# 2025-03-23.net
KiCad netlist of a schematic drawn in EasyEDA
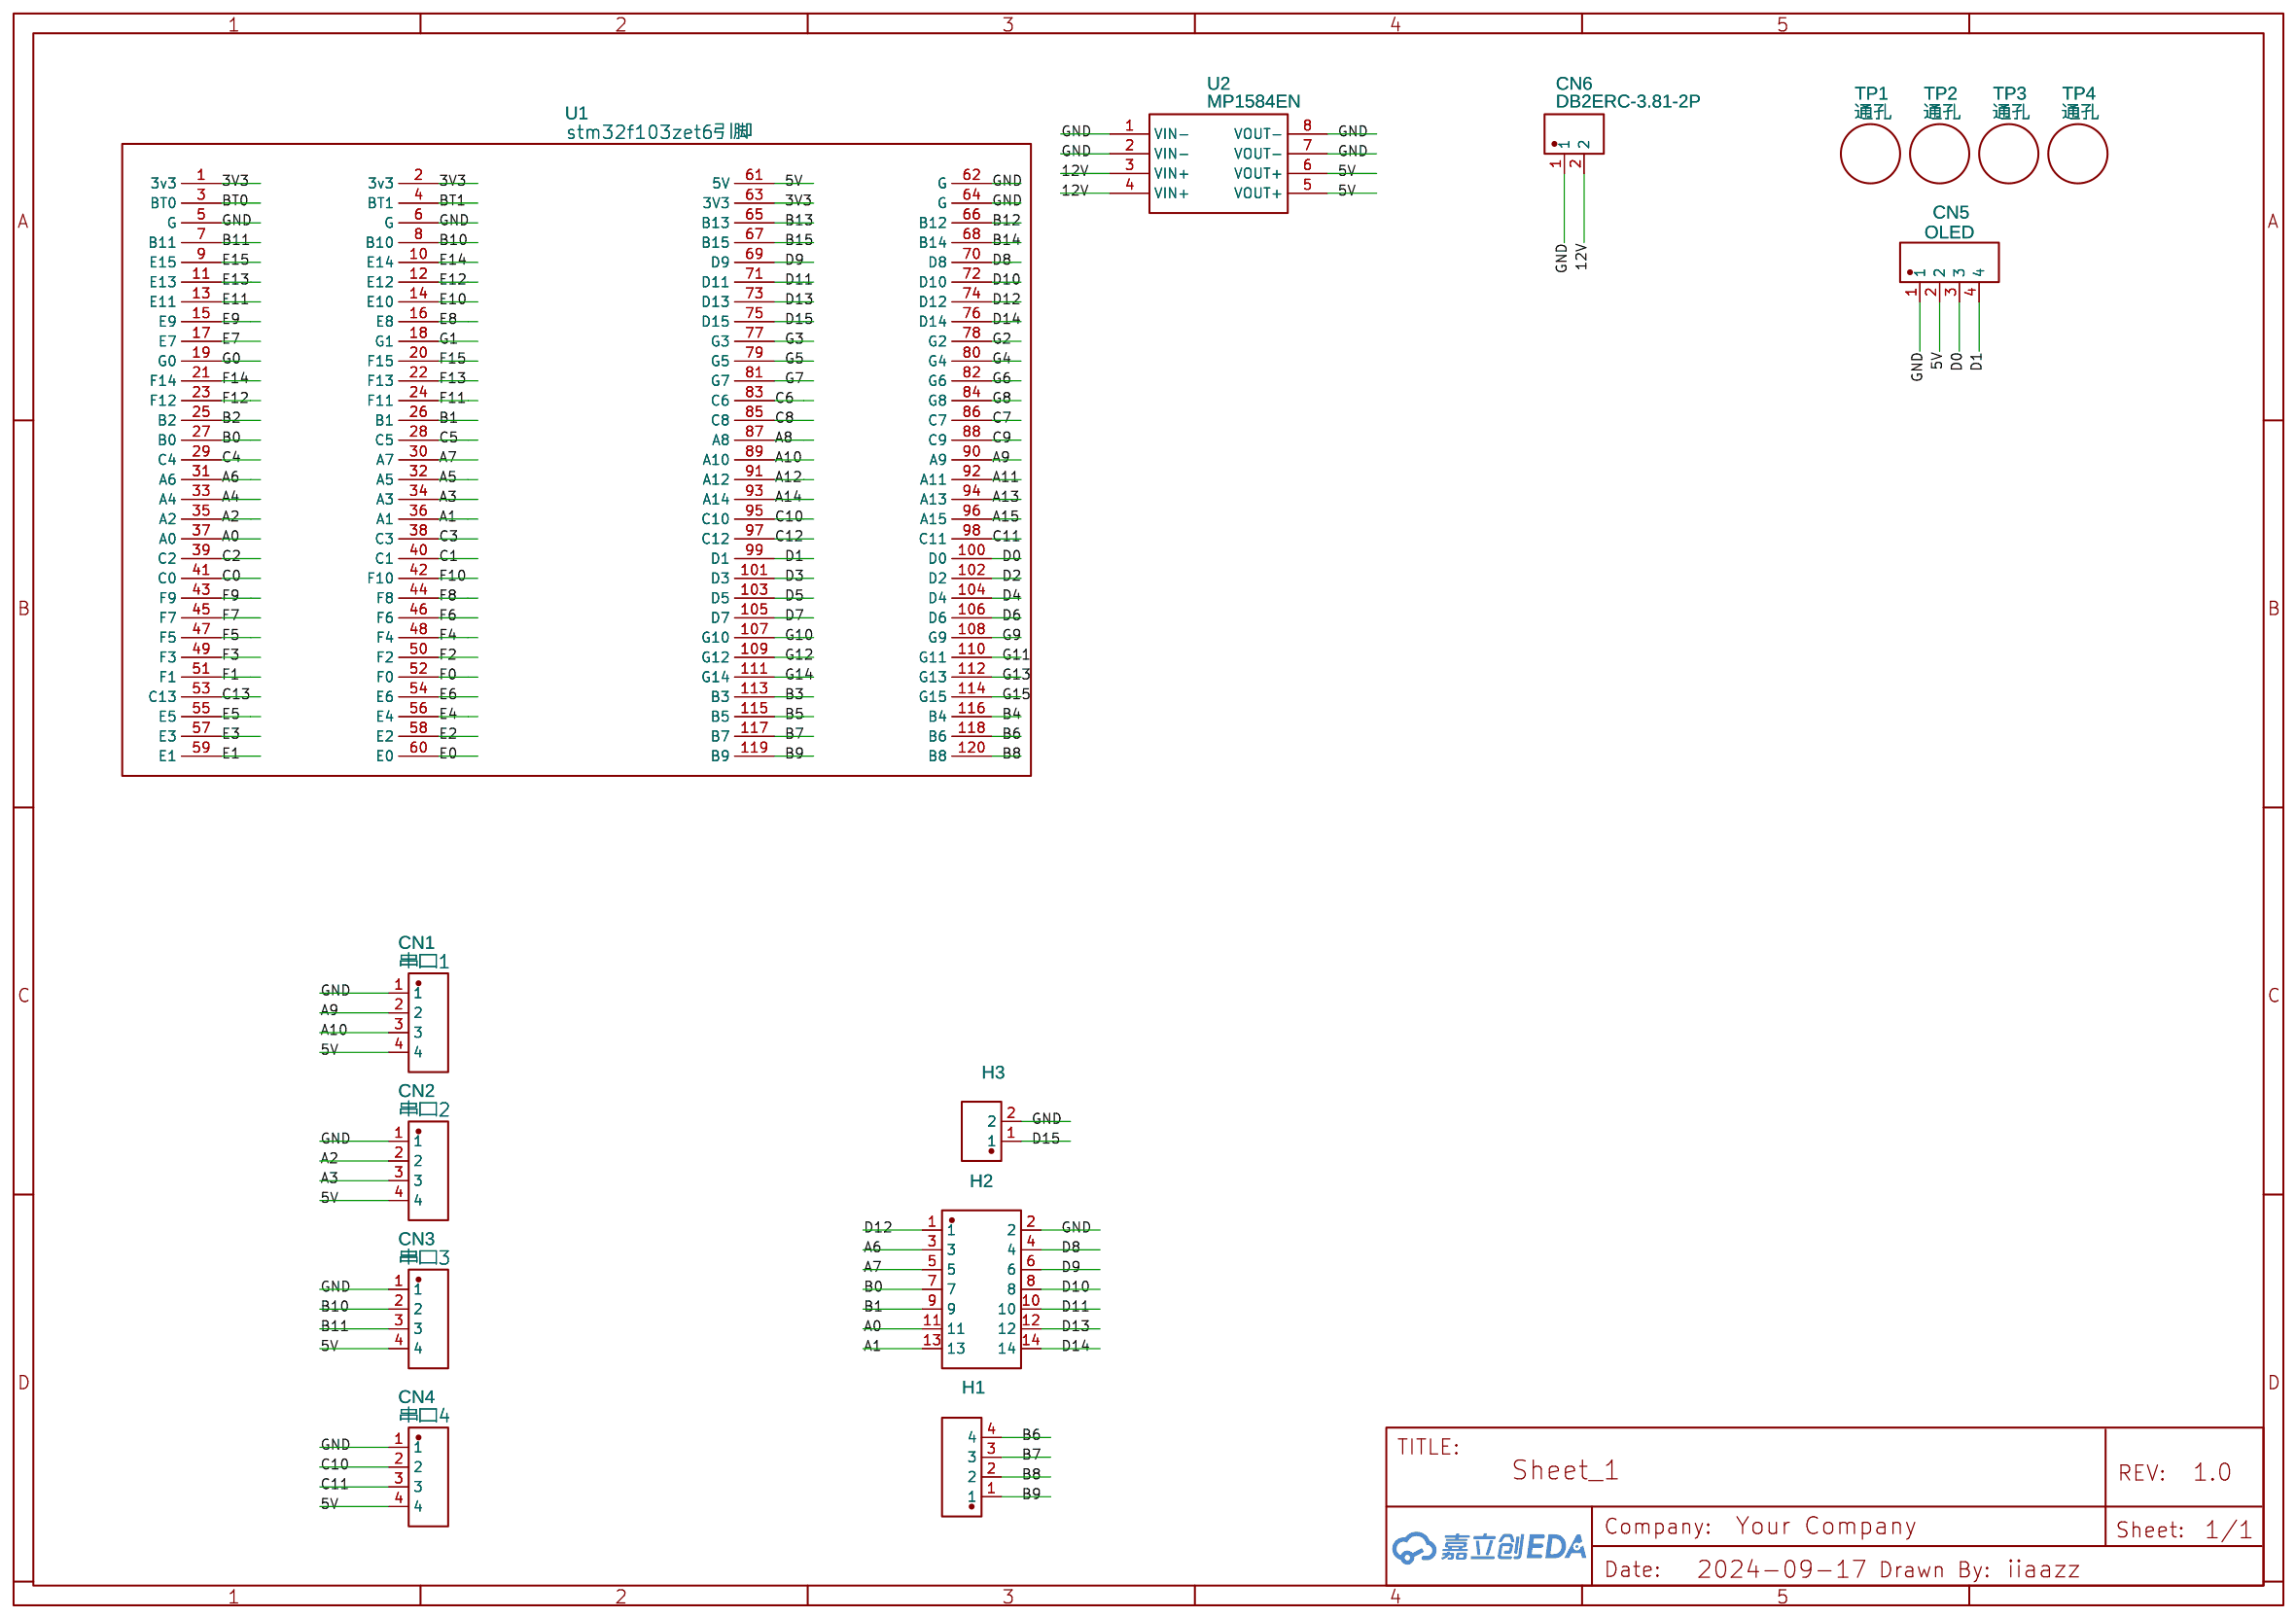
[diagram p0: schematic sheet]

(export (version "E")
  (design (tool "Eeschema 10.0.6"))
  (components
    (comp (ref "CN1")
      (value "串口1")
      (fields
        (field (name "Manufacturer Part") "ZX-XH2.54-4PWZ")
        (field (name "Manufacturer") "Megastar(兆星)")
      )
      (libsource (lib "") (part "ZX-XH2.54-4PWZ"))
    )
    (comp (ref "CN2")
      (value "串口2")
      (fields
        (field (name "Manufacturer Part") "ZX-XH2.54-4PWZ")
        (field (name "Manufacturer") "Megastar(兆星)")
      )
      (libsource (lib "") (part "ZX-XH2.54-4PWZ"))
    )
    (comp (ref "CN3")
      (value "串口3")
      (fields
        (field (name "Manufacturer Part") "ZX-XH2.54-4PWZ")
        (field (name "Manufacturer") "Megastar(兆星)")
      )
      (libsource (lib "") (part "ZX-XH2.54-4PWZ"))
    )
    (comp (ref "CN4")
      (value "串口4")
      (fields
        (field (name "Manufacturer Part") "ZX-XH2.54-4PWZ")
        (field (name "Manufacturer") "Megastar(兆星)")
      )
      (libsource (lib "") (part "ZX-XH2.54-4PWZ"))
    )
    (comp (ref "CN5")
      (value "OLED")
      (fields
        (field (name "Manufacturer Part") "ZX-XH2.54-4PWZ")
        (field (name "Manufacturer") "Megastar(兆星)")
      )
      (libsource (lib "") (part "ZX-XH2.54-4PWZ_1"))
    )
    (comp (ref "CN6")
      (value "DB2ERC-3.81-2P")
      (fields
        (field (name "Manufacturer Part") "DB2ERC-3.81-2P-GN")
        (field (name "Manufacturer") "DORABO(地博电气)")
      )
      (libsource (lib "") (part "DB2ERC-3.81-2P"))
    )
    (comp (ref "H1")
      (value "PZ254V-11-04P_C2691448")
      (fields (field (name "Manufacturer Part") "PZ254V-11-04P") (field (name "Manufacturer") "XFCN(兴飞)"))
      (libsource (lib "") (part "PZ254V-11-04P_C2691448"))
    )
    (comp (ref "H2")
      (value "PZ254V-12-14P")
      (fields (field (name "Manufacturer") "XFCN(兴飞)"))
      (libsource (lib "") (part "PZ254V-12-14P"))
    )
    (comp (ref "H3")
      (value "PZ254V-11-02P")
      (fields (field (name "Manufacturer") "XFCN(兴飞)"))
      (libsource (lib "") (part "PZ254V-11-02P"))
    )
    (comp (ref "TP1") (value "通孔") (libsource (lib "") (part "通孔")))
    (comp (ref "TP2") (value "通孔") (libsource (lib "") (part "通孔")))
    (comp (ref "TP3") (value "通孔") (libsource (lib "") (part "通孔")))
    (comp (ref "TP4") (value "通孔") (libsource (lib "") (part "通孔")))
    (comp (ref "U1") (value "stm32f103zet6引脚") (libsource (lib "") (part "stm32f103zet6引脚")))
    (comp (ref "U2") (value "MP1584EN") (libsource (lib "") (part "MP1584EN-LF-Z")))
  )
  (nets
    (net (code "1") (name "/3V3") (class "Default")
      (node (ref "U1") (pin "1") (pinfunction "3v3_1") (pintype "unspecified"))
      (node (ref "U1") (pin "2") (pinfunction "3v3_2") (pintype "unspecified"))
      (node (ref "U1") (pin "63") (pinfunction "3V3_63") (pintype "unspecified"))
    )
    (net (code "2") (name "/5V") (class "Default")
      (node (ref "CN1") (pin "4") (pinfunction "4_4") (pintype "unspecified"))
      (node (ref "CN2") (pin "4") (pinfunction "4_4") (pintype "unspecified"))
      (node (ref "CN3") (pin "4") (pinfunction "4_4") (pintype "unspecified"))
      (node (ref "CN4") (pin "4") (pinfunction "4_4") (pintype "unspecified"))
      (node (ref "CN5") (pin "2") (pinfunction "2_2") (pintype "unspecified"))
      (node (ref "U1") (pin "61") (pinfunction "5V_61") (pintype "unspecified"))
      (node (ref "U2") (pin "5") (pinfunction "VOUT+_5") (pintype "unspecified"))
      (node (ref "U2") (pin "6") (pinfunction "VOUT+_6") (pintype "unspecified"))
    )
    (net (code "3") (name "/12V") (class "Default")
      (node (ref "CN6") (pin "2") (pinfunction "2_2") (pintype "unspecified"))
      (node (ref "U2") (pin "3") (pinfunction "VIN+_3") (pintype "unspecified"))
      (node (ref "U2") (pin "4") (pinfunction "VIN+_4") (pintype "unspecified"))
    )
    (net (code "4") (name "/A0") (class "Default")
      (node (ref "H2") (pin "11") (pinfunction "11_11") (pintype "unspecified"))
      (node (ref "U1") (pin "37") (pinfunction "A0_37") (pintype "unspecified"))
    )
    (net (code "5") (name "/A1") (class "Default")
      (node (ref "H2") (pin "13") (pinfunction "13_13") (pintype "unspecified"))
      (node (ref "U1") (pin "36") (pinfunction "A1_36") (pintype "unspecified"))
    )
    (net (code "6") (name "/A2") (class "Default")
      (node (ref "CN2") (pin "2") (pinfunction "2_2") (pintype "unspecified"))
      (node (ref "U1") (pin "35") (pinfunction "A2_35") (pintype "unspecified"))
    )
    (net (code "7") (name "/A3") (class "Default")
      (node (ref "CN2") (pin "3") (pinfunction "3_3") (pintype "unspecified"))
      (node (ref "U1") (pin "34") (pinfunction "A3_34") (pintype "unspecified"))
    )
    (net (code "8") (name "/A4") (class "Default")
      (node (ref "U1") (pin "33") (pinfunction "A4_33") (pintype "unspecified"))
    )
    (net (code "9") (name "/A5") (class "Default")
      (node (ref "U1") (pin "32") (pinfunction "A5_32") (pintype "unspecified"))
    )
    (net (code "10") (name "/A6") (class "Default")
      (node (ref "H2") (pin "3") (pinfunction "3_3") (pintype "unspecified"))
      (node (ref "U1") (pin "31") (pinfunction "A6_31") (pintype "unspecified"))
    )
    (net (code "11") (name "/A7") (class "Default")
      (node (ref "H2") (pin "5") (pinfunction "5_5") (pintype "unspecified"))
      (node (ref "U1") (pin "30") (pinfunction "A7_30") (pintype "unspecified"))
    )
    (net (code "12") (name "/A8") (class "Default")
      (node (ref "U1") (pin "87") (pinfunction "A8_87") (pintype "unspecified"))
    )
    (net (code "13") (name "/A9") (class "Default")
      (node (ref "CN1") (pin "2") (pinfunction "2_2") (pintype "unspecified"))
      (node (ref "U1") (pin "90") (pinfunction "A9_90") (pintype "unspecified"))
    )
    (net (code "14") (name "/A10") (class "Default")
      (node (ref "CN1") (pin "3") (pinfunction "3_3") (pintype "unspecified"))
      (node (ref "U1") (pin "89") (pinfunction "A10_89") (pintype "unspecified"))
    )
    (net (code "15") (name "/A11") (class "Default")
      (node (ref "U1") (pin "92") (pinfunction "A11_92") (pintype "unspecified"))
    )
    (net (code "16") (name "/A12") (class "Default")
      (node (ref "U1") (pin "91") (pinfunction "A12_91") (pintype "unspecified"))
    )
    (net (code "17") (name "/A13") (class "Default")
      (node (ref "U1") (pin "94") (pinfunction "A13_94") (pintype "unspecified"))
    )
    (net (code "18") (name "/A14") (class "Default")
      (node (ref "U1") (pin "93") (pinfunction "A14_93") (pintype "unspecified"))
    )
    (net (code "19") (name "/A15") (class "Default")
      (node (ref "U1") (pin "96") (pinfunction "A15_96") (pintype "unspecified"))
    )
    (net (code "20") (name "/B0") (class "Default")
      (node (ref "H2") (pin "7") (pinfunction "7_7") (pintype "unspecified"))
      (node (ref "U1") (pin "27") (pinfunction "B0_27") (pintype "unspecified"))
    )
    (net (code "21") (name "/B1") (class "Default")
      (node (ref "H2") (pin "9") (pinfunction "9_9") (pintype "unspecified"))
      (node (ref "U1") (pin "26") (pinfunction "B1_26") (pintype "unspecified"))
    )
    (net (code "22") (name "/B2") (class "Default")
      (node (ref "U1") (pin "25") (pinfunction "B2_25") (pintype "unspecified"))
    )
    (net (code "23") (name "/B3") (class "Default")
      (node (ref "U1") (pin "113") (pinfunction "B3_113") (pintype "unspecified"))
    )
    (net (code "24") (name "/B4") (class "Default")
      (node (ref "U1") (pin "116") (pinfunction "B4_116") (pintype "unspecified"))
    )
    (net (code "25") (name "/B5") (class "Default")
      (node (ref "U1") (pin "115") (pinfunction "B5_115") (pintype "unspecified"))
    )
    (net (code "26") (name "/B6") (class "Default")
      (node (ref "H1") (pin "4") (pinfunction "4_4") (pintype "unspecified"))
      (node (ref "U1") (pin "118") (pinfunction "B6_118") (pintype "unspecified"))
    )
    (net (code "27") (name "/B7") (class "Default")
      (node (ref "H1") (pin "3") (pinfunction "3_3") (pintype "unspecified"))
      (node (ref "U1") (pin "117") (pinfunction "B7_117") (pintype "unspecified"))
    )
    (net (code "28") (name "/B8") (class "Default")
      (node (ref "H1") (pin "2") (pinfunction "2_2") (pintype "unspecified"))
      (node (ref "U1") (pin "120") (pinfunction "B8_120") (pintype "unspecified"))
    )
    (net (code "29") (name "/B9") (class "Default")
      (node (ref "H1") (pin "1") (pinfunction "1_1") (pintype "unspecified"))
      (node (ref "U1") (pin "119") (pinfunction "B9_119") (pintype "unspecified"))
    )
    (net (code "30") (name "/B10") (class "Default")
      (node (ref "CN3") (pin "2") (pinfunction "2_2") (pintype "unspecified"))
      (node (ref "U1") (pin "8") (pinfunction "B10_8") (pintype "unspecified"))
    )
    (net (code "31") (name "/B11") (class "Default")
      (node (ref "CN3") (pin "3") (pinfunction "3_3") (pintype "unspecified"))
      (node (ref "U1") (pin "7") (pinfunction "B11_7") (pintype "unspecified"))
    )
    (net (code "32") (name "/B12") (class "Default")
      (node (ref "U1") (pin "66") (pinfunction "B12_66") (pintype "unspecified"))
    )
    (net (code "33") (name "/B13") (class "Default")
      (node (ref "U1") (pin "65") (pinfunction "B13_65") (pintype "unspecified"))
    )
    (net (code "34") (name "/B14") (class "Default")
      (node (ref "U1") (pin "68") (pinfunction "B14_68") (pintype "unspecified"))
    )
    (net (code "35") (name "/B15") (class "Default")
      (node (ref "U1") (pin "67") (pinfunction "B15_67") (pintype "unspecified"))
    )
    (net (code "36") (name "/BT0") (class "Default")
      (node (ref "U1") (pin "3") (pinfunction "BT0_3") (pintype "unspecified"))
    )
    (net (code "37") (name "/BT1") (class "Default")
      (node (ref "U1") (pin "4") (pinfunction "BT1_4") (pintype "unspecified"))
    )
    (net (code "38") (name "/C0") (class "Default")
      (node (ref "U1") (pin "41") (pinfunction "C0_41") (pintype "unspecified"))
    )
    (net (code "39") (name "/C1") (class "Default")
      (node (ref "U1") (pin "40") (pinfunction "C1_40") (pintype "unspecified"))
    )
    (net (code "40") (name "/C2") (class "Default")
      (node (ref "U1") (pin "39") (pinfunction "C2_39") (pintype "unspecified"))
    )
    (net (code "41") (name "/C3") (class "Default")
      (node (ref "U1") (pin "38") (pinfunction "C3_38") (pintype "unspecified"))
    )
    (net (code "42") (name "/C4") (class "Default")
      (node (ref "U1") (pin "29") (pinfunction "C4_29") (pintype "unspecified"))
    )
    (net (code "43") (name "/C5") (class "Default")
      (node (ref "U1") (pin "28") (pinfunction "C5_28") (pintype "unspecified"))
    )
    (net (code "44") (name "/C6") (class "Default")
      (node (ref "U1") (pin "83") (pinfunction "C6_83") (pintype "unspecified"))
    )
    (net (code "45") (name "/C7") (class "Default")
      (node (ref "U1") (pin "86") (pinfunction "C7_86") (pintype "unspecified"))
    )
    (net (code "46") (name "/C8") (class "Default")
      (node (ref "U1") (pin "85") (pinfunction "C8_85") (pintype "unspecified"))
    )
    (net (code "47") (name "/C9") (class "Default")
      (node (ref "U1") (pin "88") (pinfunction "C9_88") (pintype "unspecified"))
    )
    (net (code "48") (name "/C10") (class "Default")
      (node (ref "CN4") (pin "2") (pinfunction "2_2") (pintype "unspecified"))
      (node (ref "U1") (pin "95") (pinfunction "C10_95") (pintype "unspecified"))
    )
    (net (code "49") (name "/C11") (class "Default")
      (node (ref "CN4") (pin "3") (pinfunction "3_3") (pintype "unspecified"))
      (node (ref "U1") (pin "98") (pinfunction "C11_98") (pintype "unspecified"))
    )
    (net (code "50") (name "/C12") (class "Default")
      (node (ref "U1") (pin "97") (pinfunction "C12_97") (pintype "unspecified"))
    )
    (net (code "51") (name "/C13") (class "Default")
      (node (ref "U1") (pin "53") (pinfunction "C13_53") (pintype "unspecified"))
    )
    (net (code "52") (name "/D0") (class "Default")
      (node (ref "CN5") (pin "3") (pinfunction "3_3") (pintype "unspecified"))
      (node (ref "U1") (pin "100") (pinfunction "D0_100") (pintype "unspecified"))
    )
    (net (code "53") (name "/D1") (class "Default")
      (node (ref "CN5") (pin "4") (pinfunction "4_4") (pintype "unspecified"))
      (node (ref "U1") (pin "99") (pinfunction "D1_99") (pintype "unspecified"))
    )
    (net (code "54") (name "/D2") (class "Default")
      (node (ref "U1") (pin "102") (pinfunction "D2_102") (pintype "unspecified"))
    )
    (net (code "55") (name "/D3") (class "Default")
      (node (ref "U1") (pin "101") (pinfunction "D3_101") (pintype "unspecified"))
    )
    (net (code "56") (name "/D4") (class "Default")
      (node (ref "U1") (pin "104") (pinfunction "D4_104") (pintype "unspecified"))
    )
    (net (code "57") (name "/D5") (class "Default")
      (node (ref "U1") (pin "103") (pinfunction "D5_103") (pintype "unspecified"))
    )
    (net (code "58") (name "/D6") (class "Default")
      (node (ref "U1") (pin "106") (pinfunction "D6_106") (pintype "unspecified"))
    )
    (net (code "59") (name "/D7") (class "Default")
      (node (ref "U1") (pin "105") (pinfunction "D7_105") (pintype "unspecified"))
    )
    (net (code "60") (name "/D8") (class "Default")
      (node (ref "H2") (pin "4") (pinfunction "4_4") (pintype "unspecified"))
      (node (ref "U1") (pin "70") (pinfunction "D8_70") (pintype "unspecified"))
    )
    (net (code "61") (name "/D9") (class "Default")
      (node (ref "H2") (pin "6") (pinfunction "6_6") (pintype "unspecified"))
      (node (ref "U1") (pin "69") (pinfunction "D9_69") (pintype "unspecified"))
    )
    (net (code "62") (name "/D10") (class "Default")
      (node (ref "H2") (pin "8") (pinfunction "8_8") (pintype "unspecified"))
      (node (ref "U1") (pin "72") (pinfunction "D10_72") (pintype "unspecified"))
    )
    (net (code "63") (name "/D11") (class "Default")
      (node (ref "H2") (pin "10") (pinfunction "10_10") (pintype "unspecified"))
      (node (ref "U1") (pin "71") (pinfunction "D11_71") (pintype "unspecified"))
    )
    (net (code "64") (name "/D12") (class "Default")
      (node (ref "H2") (pin "1") (pinfunction "1_1") (pintype "unspecified"))
      (node (ref "U1") (pin "74") (pinfunction "D12_74") (pintype "unspecified"))
    )
    (net (code "65") (name "/D13") (class "Default")
      (node (ref "H2") (pin "12") (pinfunction "12_12") (pintype "unspecified"))
      (node (ref "U1") (pin "73") (pinfunction "D13_73") (pintype "unspecified"))
    )
    (net (code "66") (name "/D14") (class "Default")
      (node (ref "H2") (pin "14") (pinfunction "14_14") (pintype "unspecified"))
      (node (ref "U1") (pin "76") (pinfunction "D14_76") (pintype "unspecified"))
    )
    (net (code "67") (name "/D15") (class "Default")
      (node (ref "H3") (pin "1") (pinfunction "1_1") (pintype "unspecified"))
      (node (ref "U1") (pin "75") (pinfunction "D15_75") (pintype "unspecified"))
    )
    (net (code "68") (name "/E0") (class "Default")
      (node (ref "U1") (pin "60") (pinfunction "E0_60") (pintype "unspecified"))
    )
    (net (code "69") (name "/E1") (class "Default")
      (node (ref "U1") (pin "59") (pinfunction "E1_59") (pintype "unspecified"))
    )
    (net (code "70") (name "/E2") (class "Default")
      (node (ref "U1") (pin "58") (pinfunction "E2_58") (pintype "unspecified"))
    )
    (net (code "71") (name "/E3") (class "Default")
      (node (ref "U1") (pin "57") (pinfunction "E3_57") (pintype "unspecified"))
    )
    (net (code "72") (name "/E4") (class "Default")
      (node (ref "U1") (pin "56") (pinfunction "E4_56") (pintype "unspecified"))
    )
    (net (code "73") (name "/E5") (class "Default")
      (node (ref "U1") (pin "55") (pinfunction "E5_55") (pintype "unspecified"))
    )
    (net (code "74") (name "/E6") (class "Default")
      (node (ref "U1") (pin "54") (pinfunction "E6_54") (pintype "unspecified"))
    )
    (net (code "75") (name "/E7") (class "Default")
      (node (ref "U1") (pin "17") (pinfunction "E7_17") (pintype "unspecified"))
    )
    (net (code "76") (name "/E8") (class "Default")
      (node (ref "U1") (pin "16") (pinfunction "E8_16") (pintype "unspecified"))
    )
    (net (code "77") (name "/E9") (class "Default")
      (node (ref "U1") (pin "15") (pinfunction "E9_15") (pintype "unspecified"))
    )
    (net (code "78") (name "/E10") (class "Default")
      (node (ref "U1") (pin "14") (pinfunction "E10_14") (pintype "unspecified"))
    )
    (net (code "79") (name "/E11") (class "Default")
      (node (ref "U1") (pin "13") (pinfunction "E11_13") (pintype "unspecified"))
    )
    (net (code "80") (name "/E12") (class "Default")
      (node (ref "U1") (pin "12") (pinfunction "E12_12") (pintype "unspecified"))
    )
    (net (code "81") (name "/E13") (class "Default")
      (node (ref "U1") (pin "11") (pinfunction "E13_11") (pintype "unspecified"))
    )
    (net (code "82") (name "/E14") (class "Default")
      (node (ref "U1") (pin "10") (pinfunction "E14_10") (pintype "unspecified"))
    )
    (net (code "83") (name "/E15") (class "Default")
      (node (ref "U1") (pin "9") (pinfunction "E15_9") (pintype "unspecified"))
    )
    (net (code "84") (name "/F0") (class "Default")
      (node (ref "U1") (pin "52") (pinfunction "F0_52") (pintype "unspecified"))
    )
    (net (code "85") (name "/F1") (class "Default")
      (node (ref "U1") (pin "51") (pinfunction "F1_51") (pintype "unspecified"))
    )
    (net (code "86") (name "/F2") (class "Default")
      (node (ref "U1") (pin "50") (pinfunction "F2_50") (pintype "unspecified"))
    )
    (net (code "87") (name "/F3") (class "Default")
      (node (ref "U1") (pin "49") (pinfunction "F3_49") (pintype "unspecified"))
    )
    (net (code "88") (name "/F4") (class "Default")
      (node (ref "U1") (pin "48") (pinfunction "F4_48") (pintype "unspecified"))
    )
    (net (code "89") (name "/F5") (class "Default")
      (node (ref "U1") (pin "47") (pinfunction "F5_47") (pintype "unspecified"))
    )
    (net (code "90") (name "/F6") (class "Default")
      (node (ref "U1") (pin "46") (pinfunction "F6_46") (pintype "unspecified"))
    )
    (net (code "91") (name "/F7") (class "Default")
      (node (ref "U1") (pin "45") (pinfunction "F7_45") (pintype "unspecified"))
    )
    (net (code "92") (name "/F8") (class "Default")
      (node (ref "U1") (pin "44") (pinfunction "F8_44") (pintype "unspecified"))
    )
    (net (code "93") (name "/F9") (class "Default")
      (node (ref "U1") (pin "43") (pinfunction "F9_43") (pintype "unspecified"))
    )
    (net (code "94") (name "/F10") (class "Default")
      (node (ref "U1") (pin "42") (pinfunction "F10_42") (pintype "unspecified"))
    )
    (net (code "95") (name "/F11") (class "Default")
      (node (ref "U1") (pin "24") (pinfunction "F11_24") (pintype "unspecified"))
    )
    (net (code "96") (name "/F12") (class "Default")
      (node (ref "U1") (pin "23") (pinfunction "F12_23") (pintype "unspecified"))
    )
    (net (code "97") (name "/F13") (class "Default")
      (node (ref "U1") (pin "22") (pinfunction "F13_22") (pintype "unspecified"))
    )
    (net (code "98") (name "/F14") (class "Default")
      (node (ref "U1") (pin "21") (pinfunction "F14_21") (pintype "unspecified"))
    )
    (net (code "99") (name "/F15") (class "Default")
      (node (ref "U1") (pin "20") (pinfunction "F15_20") (pintype "unspecified"))
    )
    (net (code "100") (name "/G0") (class "Default")
      (node (ref "U1") (pin "19") (pinfunction "G0_19") (pintype "unspecified"))
    )
    (net (code "101") (name "/G1") (class "Default")
      (node (ref "U1") (pin "18") (pinfunction "G1_18") (pintype "unspecified"))
    )
    (net (code "102") (name "/G2") (class "Default")
      (node (ref "U1") (pin "78") (pinfunction "G2_78") (pintype "unspecified"))
    )
    (net (code "103") (name "/G3") (class "Default")
      (node (ref "U1") (pin "77") (pinfunction "G3_77") (pintype "unspecified"))
    )
    (net (code "104") (name "/G4") (class "Default")
      (node (ref "U1") (pin "80") (pinfunction "G4_80") (pintype "unspecified"))
    )
    (net (code "105") (name "/G5") (class "Default")
      (node (ref "U1") (pin "79") (pinfunction "G5_79") (pintype "unspecified"))
    )
    (net (code "106") (name "/G6") (class "Default")
      (node (ref "U1") (pin "82") (pinfunction "G6_82") (pintype "unspecified"))
    )
    (net (code "107") (name "/G7") (class "Default")
      (node (ref "U1") (pin "81") (pinfunction "G7_81") (pintype "unspecified"))
    )
    (net (code "108") (name "/G8") (class "Default")
      (node (ref "U1") (pin "84") (pinfunction "G8_84") (pintype "unspecified"))
    )
    (net (code "109") (name "/G9") (class "Default")
      (node (ref "U1") (pin "108") (pinfunction "G9_108") (pintype "unspecified"))
    )
    (net (code "110") (name "/G10") (class "Default")
      (node (ref "U1") (pin "107") (pinfunction "G10_107") (pintype "unspecified"))
    )
    (net (code "111") (name "/G11") (class "Default")
      (node (ref "U1") (pin "110") (pinfunction "G11_110") (pintype "unspecified"))
    )
    (net (code "112") (name "/G12") (class "Default")
      (node (ref "U1") (pin "109") (pinfunction "G12_109") (pintype "unspecified"))
    )
    (net (code "113") (name "/G13") (class "Default")
      (node (ref "U1") (pin "112") (pinfunction "G13_112") (pintype "unspecified"))
    )
    (net (code "114") (name "/G14") (class "Default")
      (node (ref "U1") (pin "111") (pinfunction "G14_111") (pintype "unspecified"))
    )
    (net (code "115") (name "/G15") (class "Default")
      (node (ref "U1") (pin "114") (pinfunction "G15_114") (pintype "unspecified"))
    )
    (net (code "116") (name "/GND") (class "Default")
      (node (ref "CN1") (pin "1") (pinfunction "1_1") (pintype "unspecified"))
      (node (ref "CN2") (pin "1") (pinfunction "1_1") (pintype "unspecified"))
      (node (ref "CN3") (pin "1") (pinfunction "1_1") (pintype "unspecified"))
      (node (ref "CN4") (pin "1") (pinfunction "1_1") (pintype "unspecified"))
      (node (ref "CN5") (pin "1") (pinfunction "1_1") (pintype "unspecified"))
      (node (ref "CN6") (pin "1") (pinfunction "1_1") (pintype "unspecified"))
      (node (ref "H2") (pin "2") (pinfunction "2_2") (pintype "unspecified"))
      (node (ref "H3") (pin "2") (pinfunction "2_2") (pintype "unspecified"))
      (node (ref "U1") (pin "5") (pinfunction "G_5") (pintype "unspecified"))
      (node (ref "U1") (pin "6") (pinfunction "G_6") (pintype "unspecified"))
      (node (ref "U1") (pin "62") (pinfunction "G_62") (pintype "unspecified"))
      (node (ref "U1") (pin "64") (pinfunction "G_64") (pintype "unspecified"))
      (node (ref "U2") (pin "1") (pinfunction "VIN-_1") (pintype "unspecified"))
      (node (ref "U2") (pin "2") (pinfunction "VIN-_2") (pintype "unspecified"))
      (node (ref "U2") (pin "7") (pinfunction "VOUT-_7") (pintype "unspecified"))
      (node (ref "U2") (pin "8") (pinfunction "VOUT-_8") (pintype "unspecified"))
    )
  )
)
